# ESP32_USBC.net
KiCad netlist of a schematic drawn in Altium Designer
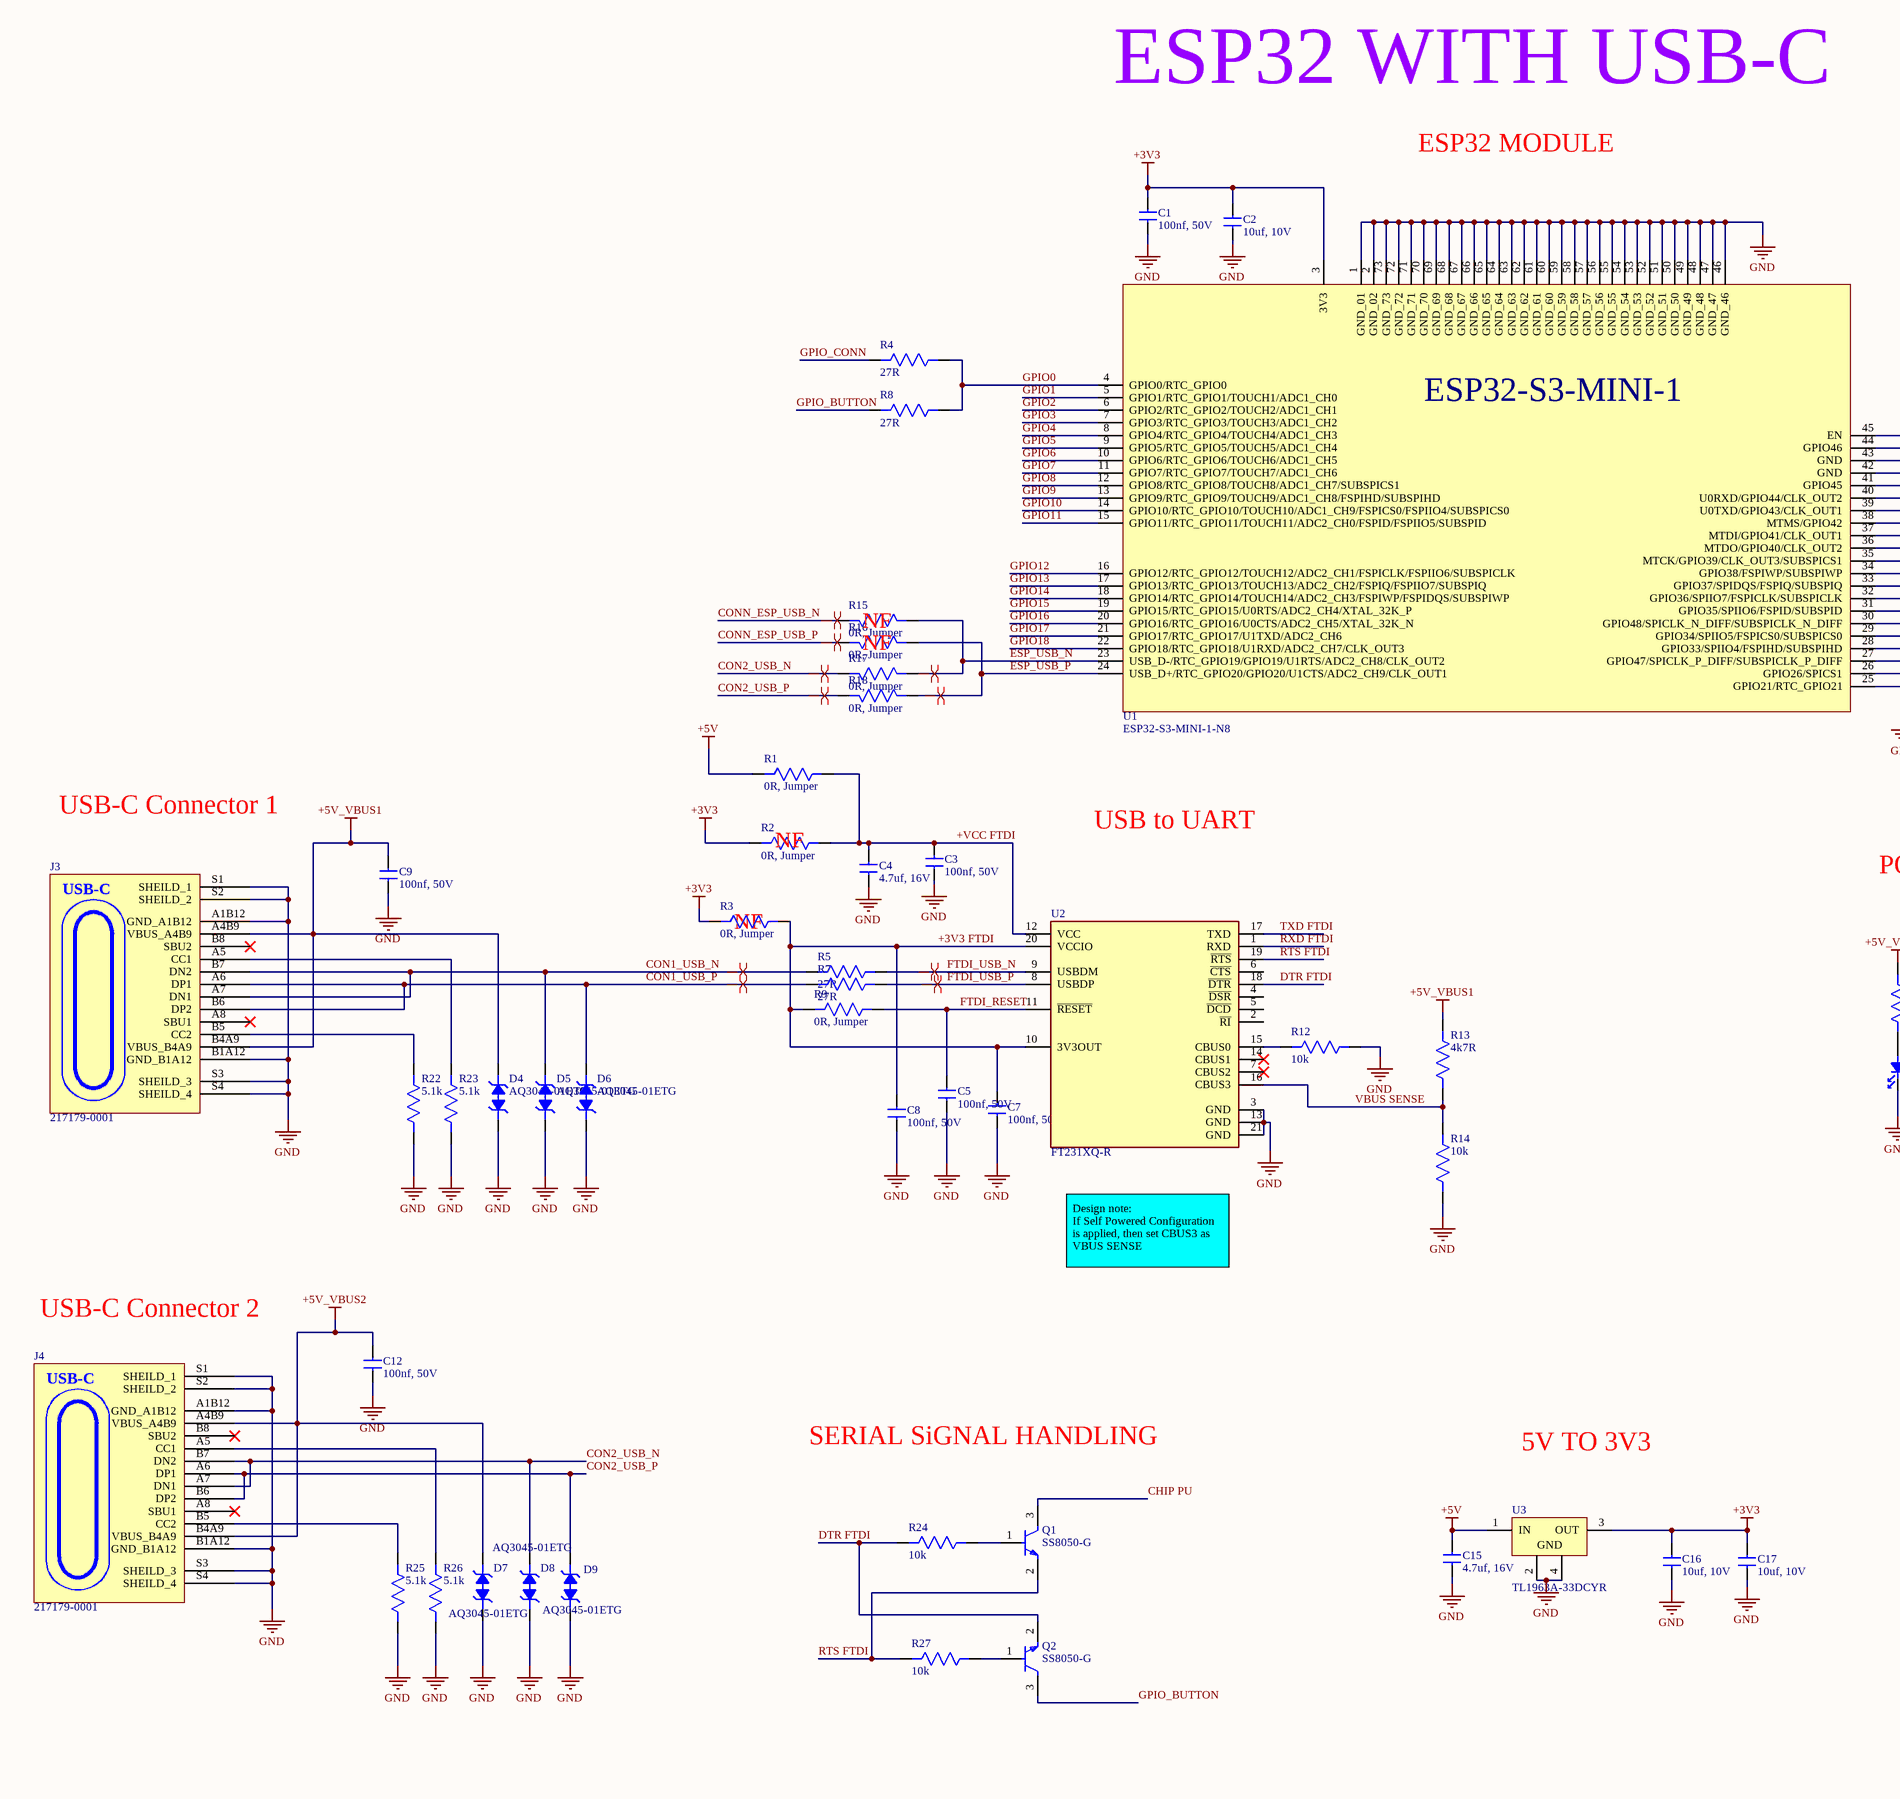
[diagram p0: ESP32_USBC.SchDoc, left]
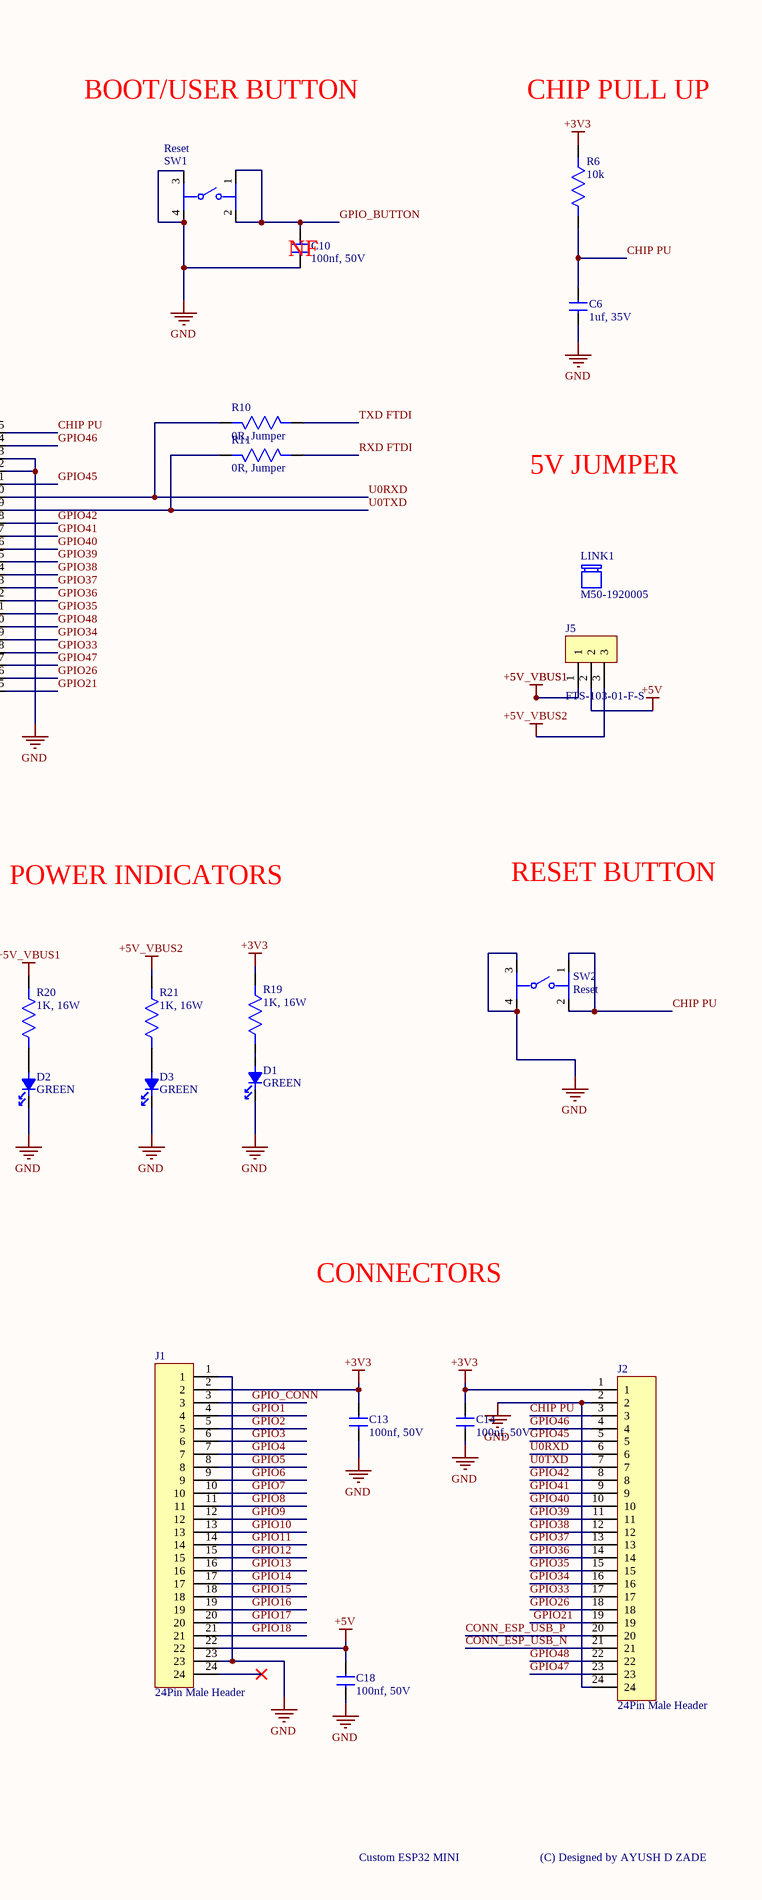
[diagram p1: ESP32_USBC.SchDoc, right]

(export (version "E")
  (design (tool "Eeschema 10.0.6"))
  (components
    (comp (ref "C1")
      (value "100nf, 50V")
      (footprint "CAPC1005X70N")
      (description "CAP CER 0.1UF 50V X7R 0402")
      (fields
        (field (name "MANUFACTURER") "Samsung Electro-Mechanics")
        (field (name "MANUFACTURER PART NUMBER") "CL05B104KB5NNWC")
      )
      (libsource (lib "Schlib") (part "CL05B104KB5NNWC"))
    )
    (comp (ref "C2")
      (value "10uf, 10V")
      (footprint "CAPC1005X70N")
      (description "CAP CER 10UF 10V X5R 0402")
      (fields
        (field (name "MANUFACTURER") "Samsung Electro-Mechanics")
        (field (name "MANUFACTURER PART NUMBER") "CL05A106MP5NRNC")
      )
      (libsource (lib "Schlib") (part "CL05A106MP5NRNC"))
    )
    (comp (ref "C3")
      (value "100nf, 50V")
      (footprint "CAPC1005X70N")
      (description "CAP CER 0.1UF 50V X7R 0402")
      (fields
        (field (name "MANUFACTURER") "Samsung Electro-Mechanics")
        (field (name "MANUFACTURER PART NUMBER") "CL05B104KB5NNWC")
      )
      (libsource (lib "Schlib") (part "CL05B104KB5NNWC"))
    )
    (comp (ref "C4")
      (value "4.7uf, 16V")
      (footprint "CAPC1005X70N")
      (description "4.7 µF ±20% 16V Ceramic Capacitor X5R 0402 (1005 Metric)")
      (fields
        (field (name "MANUFACTURER") "Samsung")
        (field (name "MANUFACTURER PART NUMBER") "CL05A475MO5NUNC")
      )
      (libsource (lib "Schlib") (part "CL05A475MO5NUNC"))
    )
    (comp (ref "C5")
      (value "100nf, 50V")
      (footprint "CAPC1005X70N")
      (description "CAP CER 0.1UF 50V X7R 0402")
      (fields
        (field (name "MANUFACTURER") "Samsung Electro-Mechanics")
        (field (name "MANUFACTURER PART NUMBER") "CL05B104KB5NNWC")
      )
      (libsource (lib "Schlib") (part "CL05B104KB5NNWC"))
    )
    (comp (ref "C6")
      (value "1uf, 35V")
      (footprint "CAPC1005X70N")
      (description "CAP CER 1UF 35V X5R 0402")
      (fields
        (field (name "MANUFACTURER") "Samsung Electro-Mechanics")
        (field (name "MANUFACTURER PART NUMBER") "CL05A105KL5NRNC")
      )
      (libsource (lib "Schlib") (part "CL05A105KL5NRNC"))
    )
    (comp (ref "C7")
      (value "100nf, 50V")
      (footprint "CAPC1005X70N")
      (description "CAP CER 0.1UF 50V X7R 0402")
      (fields
        (field (name "MANUFACTURER") "Samsung Electro-Mechanics")
        (field (name "MANUFACTURER PART NUMBER") "CL05B104KB5NNWC")
      )
      (libsource (lib "Schlib") (part "CL05B104KB5NNWC"))
    )
    (comp (ref "C8")
      (value "100nf, 50V")
      (footprint "CAPC1005X70N")
      (description "CAP CER 0.1UF 50V X7R 0402")
      (fields
        (field (name "MANUFACTURER") "Samsung Electro-Mechanics")
        (field (name "MANUFACTURER PART NUMBER") "CL05B104KB5NNWC")
      )
      (libsource (lib "Schlib") (part "CL05B104KB5NNWC"))
    )
    (comp (ref "C9")
      (value "100nf, 50V")
      (footprint "CAPC1005X70N")
      (description "CAP CER 0.1UF 50V X7R 0402")
      (fields
        (field (name "MANUFACTURER") "Samsung Electro-Mechanics")
        (field (name "MANUFACTURER PART NUMBER") "CL05B104KB5NNWC")
      )
      (libsource (lib "Schlib") (part "CL05B104KB5NNWC"))
    )
    (comp (ref "C10")
      (value "100nf, 50V")
      (footprint "CAPC1005X70N")
      (description "CAP CER 0.1UF 50V X7R 0402")
      (fields
        (field (name "MANUFACTURER") "Samsung Electro-Mechanics")
        (field (name "MANUFACTURER PART NUMBER") "CL05B104KB5NNWC")
      )
      (libsource (lib "Schlib") (part "CL05B104KB5NNWC"))
    )
    (comp (ref "C12")
      (value "100nf, 50V")
      (footprint "CAPC1005X70N")
      (description "CAP CER 0.1UF 50V X7R 0402")
      (fields
        (field (name "MANUFACTURER") "Samsung Electro-Mechanics")
        (field (name "MANUFACTURER PART NUMBER") "CL05B104KB5NNWC")
      )
      (libsource (lib "Schlib") (part "CL05B104KB5NNWC"))
    )
    (comp (ref "C13")
      (value "100nf, 50V")
      (footprint "CAPC1005X70N")
      (description "CAP CER 0.1UF 50V X7R 0402")
      (fields
        (field (name "MANUFACTURER") "Samsung Electro-Mechanics")
        (field (name "MANUFACTURER PART NUMBER") "CL05B104KB5NNWC")
      )
      (libsource (lib "Schlib") (part "CL05B104KB5NNWC"))
    )
    (comp (ref "C14")
      (value "100nf, 50V")
      (footprint "CAPC1005X70N")
      (description "CAP CER 0.1UF 50V X7R 0402")
      (fields
        (field (name "MANUFACTURER") "Samsung Electro-Mechanics")
        (field (name "MANUFACTURER PART NUMBER") "CL05B104KB5NNWC")
      )
      (libsource (lib "Schlib") (part "CL05B104KB5NNWC"))
    )
    (comp (ref "C15")
      (value "4.7uf, 16V")
      (footprint "CAPC1005X70N")
      (description "4.7 µF ±20% 16V Ceramic Capacitor X5R 0402 (1005 Metric)")
      (fields
        (field (name "MANUFACTURER") "Samsung")
        (field (name "MANUFACTURER PART NUMBER") "CL05A475MO5NUNC")
      )
      (libsource (lib "Schlib") (part "CL05A475MO5NUNC"))
    )
    (comp (ref "C16")
      (value "10uf, 10V")
      (footprint "CAPC1005X70N")
      (description "CAP CER 10UF 10V X5R 0402")
      (fields
        (field (name "MANUFACTURER") "Samsung Electro-Mechanics")
        (field (name "MANUFACTURER PART NUMBER") "CL05A106MP5NRNC")
      )
      (libsource (lib "Schlib") (part "CL05A106MP5NRNC"))
    )
    (comp (ref "C17")
      (value "10uf, 10V")
      (footprint "CAPC1005X70N")
      (description "CAP CER 10UF 10V X5R 0402")
      (fields
        (field (name "MANUFACTURER") "Samsung Electro-Mechanics")
        (field (name "MANUFACTURER PART NUMBER") "CL05A106MP5NRNC")
      )
      (libsource (lib "Schlib") (part "CL05A106MP5NRNC"))
    )
    (comp (ref "C18")
      (value "100nf, 50V")
      (footprint "CAPC1005X70N")
      (description "CAP CER 0.1UF 50V X7R 0402")
      (fields
        (field (name "MANUFACTURER") "Samsung Electro-Mechanics")
        (field (name "MANUFACTURER PART NUMBER") "CL05B104KB5NNWC")
      )
      (libsource (lib "Schlib") (part "CL05B104KB5NNWC"))
    )
    (comp (ref "D1")
      (value "GREEN")
      (footprint "LEDC1005X35N")
      (description "LED YLW-GRN 0402 SMD")
      (fields
        (field (name "MANUFACTURER") "Vishay")
        (field (name "MANUFACTURER PART NUMBER") "VLMG1500-GS08")
      )
      (libsource (lib "Schlib") (part "VLMG1500-GS08"))
    )
    (comp (ref "D2")
      (value "GREEN")
      (footprint "LEDC1005X35N")
      (description "LED YLW-GRN 0402 SMD")
      (fields
        (field (name "MANUFACTURER") "Vishay")
        (field (name "MANUFACTURER PART NUMBER") "VLMG1500-GS08")
      )
      (libsource (lib "Schlib") (part "VLMG1500-GS08"))
    )
    (comp (ref "D3")
      (value "GREEN")
      (footprint "LEDC1005X35N")
      (description "LED YLW-GRN 0402 SMD")
      (fields
        (field (name "MANUFACTURER") "Vishay")
        (field (name "MANUFACTURER PART NUMBER") "VLMG1500-GS08")
      )
      (libsource (lib "Schlib") (part "VLMG1500-GS08"))
    )
    (comp (ref "D4")
      (value "AQ3045-01ETG")
      (footprint "SOD882")
      (description "TVS DIODE 5.3VWM 12VC SOD882")
      (fields (field (name "MANUFACTURER") "Littelfuse") (field (name "LCSC PART NO.") "C3710326"))
      (libsource (lib "Schlib") (part "AQ3045-01ETG"))
    )
    (comp (ref "D5")
      (value "AQ3045-01ETG")
      (footprint "SOD882")
      (description "TVS DIODE 5.3VWM 12VC SOD882")
      (fields (field (name "MANUFACTURER") "Littelfuse") (field (name "LCSC PART NO.") "C3710326"))
      (libsource (lib "Schlib") (part "AQ3045-01ETG"))
    )
    (comp (ref "D6")
      (value "AQ3045-01ETG")
      (footprint "SOD882")
      (description "TVS DIODE 5.3VWM 12VC SOD882")
      (fields (field (name "MANUFACTURER") "Littelfuse") (field (name "LCSC PART NO.") "C3710326"))
      (libsource (lib "Schlib") (part "AQ3045-01ETG"))
    )
    (comp (ref "D7")
      (value "AQ3045-01ETG")
      (footprint "SOD882")
      (description "TVS DIODE 5.3VWM 12VC SOD882")
      (fields (field (name "MANUFACTURER") "Littelfuse") (field (name "LCSC PART NO.") "C3710326"))
      (libsource (lib "Schlib") (part "AQ3045-01ETG"))
    )
    (comp (ref "D8")
      (value "AQ3045-01ETG")
      (footprint "SOD882")
      (description "TVS DIODE 5.3VWM 12VC SOD882")
      (fields (field (name "MANUFACTURER") "Littelfuse") (field (name "LCSC PART NO.") "C3710326"))
      (libsource (lib "Schlib") (part "AQ3045-01ETG"))
    )
    (comp (ref "D9")
      (value "AQ3045-01ETG")
      (footprint "SOD882")
      (description "TVS DIODE 5.3VWM 12VC SOD882")
      (fields (field (name "MANUFACTURER") "Littelfuse") (field (name "LCSC PART NO.") "C3710326"))
      (libsource (lib "Schlib") (part "AQ3045-01ETG"))
    )
    (comp (ref "J1")
      (value "24Pin Male Header")
      (footprint "HDR_01x24_2.54mm")
      (description "CONN HEADER VERT 24POS 2.54MM")
      (fields (field (name "MANUFACTURER") "Molex") (field (name "MANUFACTURER PART NUMBER") "22-28-4245"))
      (libsource (lib "") (part "0022284245_1"))
    )
    (comp (ref "J2")
      (value "24Pin Male Header")
      (footprint "HDR_01x24_2.54mm")
      (description "CONN HEADER VERT 24POS 2.54MM")
      (fields (field (name "MANUFACTURER") "Molex") (field (name "MANUFACTURER PART NUMBER") "22-28-4245"))
      (libsource (lib "Schlib") (part "0022284245"))
    )
    (comp (ref "J3")
      (value "217179-0001")
      (footprint "FP-2171790001-MFG")
      (description "CONN RCP USB2.0 TYP C 24P SMD RA")
      (fields (field (name "MANUFACTURER") "Molex") (field (name "LCSC PART NO.") "C3197684"))
      (libsource (lib "Schlib") (part "217179-0001"))
    )
    (comp (ref "J4")
      (value "217179-0001")
      (footprint "FP-2171790001-MFG")
      (description "CONN RCP USB2.0 TYP C 24P SMD RA")
      (fields (field (name "MANUFACTURER") "Molex") (field (name "LCSC PART NO.") "C3197684"))
      (libsource (lib "Schlib") (part "217179-0001"))
    )
    (comp (ref "J5")
      (value "FTS-103-01-F-S")
      (footprint "HDR_01x03_1.27")
      (description "CONN HEADER VERT 3POS 1.27MM")
      (fields (field (name "MANUFACTURER") "Samtec") (field (name "LCSC PART NO.") "C3333578"))
      (libsource (lib "Schlib") (part "FTS-103-01-F-S"))
    )
    (comp (ref "LINK1")
      (value "M50-1920005")
      (description "CONN SHUNT 1.27MM RED")
      (fields (field (name "MANUFACTURER") "Harwin") (field (name "LCSC PART NO.") "C6985646"))
      (libsource (lib "Schlib") (part "M50-1920005"))
    )
    (comp (ref "Q1")
      (value "SS8050-G")
      (footprint "FP-SS8050-G-IPC_B")
      (description "TRANS NPN 25V 1.5A SOT-23-3")
      (fields (field (name "MANUFACTURER") "Comchip") (field (name "LCSC PART NO.") "C164886"))
      (libsource (lib "Schlib") (part "SS8050-G"))
    )
    (comp (ref "Q2")
      (value "SS8050-G")
      (footprint "FP-SS8050-G-IPC_B")
      (description "TRANS NPN 25V 1.5A SOT-23-3")
      (fields (field (name "MANUFACTURER") "Comchip") (field (name "LCSC PART NO.") "C164886"))
      (libsource (lib "Schlib") (part "SS8050-G"))
    )
    (comp (ref "R1")
      (value "0R, Jumper")
      (footprint "RESC1005X37N")
      (description "RES 0 OHM JUMPER 1/16W 0402")
      (fields
        (field (name "MANUFACTURER") "Yageo")
        (field (name "MANUFACTURER PART NUMBER") "RC0402FR-070RL")
      )
      (libsource (lib "Schlib") (part "RC0402FR-070RL"))
    )
    (comp (ref "R2")
      (value "0R, Jumper")
      (footprint "RESC1005X37N")
      (description "RES 0 OHM JUMPER 1/16W 0402")
      (fields
        (field (name "MANUFACTURER") "Yageo")
        (field (name "MANUFACTURER PART NUMBER") "RC0402FR-070RL")
      )
      (libsource (lib "Schlib") (part "RC0402FR-070RL"))
    )
    (comp (ref "R3")
      (value "0R, Jumper")
      (footprint "RESC1005X37N")
      (description "RES 0 OHM JUMPER 1/16W 0402")
      (fields
        (field (name "MANUFACTURER") "Yageo")
        (field (name "MANUFACTURER PART NUMBER") "RC0402FR-070RL")
      )
      (libsource (lib "Schlib") (part "RC0402FR-070RL"))
    )
    (comp (ref "R4")
      (value "27R")
      (footprint "RESC1005X37N")
      (description "RES 27 OHM 1% 1/16W 0402")
      (fields
        (field (name "MANUFACTURER") "Yageo")
        (field (name "MANUFACTURER PART NUMBER") "RC0402FR-0727RL")
      )
      (libsource (lib "Schlib") (part "RC0402FR-0727RL"))
    )
    (comp (ref "R5")
      (value "27R")
      (footprint "RESC1005X37N")
      (description "RES 27 OHM 1% 1/16W 0402")
      (fields
        (field (name "MANUFACTURER") "Yageo")
        (field (name "MANUFACTURER PART NUMBER") "RC0402FR-0727RL")
      )
      (libsource (lib "Schlib") (part "RC0402FR-0727RL"))
    )
    (comp (ref "R6")
      (value "10k")
      (footprint "RESC1005X37N")
      (description "RES SMD 10K OHM 1% 1/16W 0402")
      (fields
        (field (name "MANUFACTURER") "Yageo Group")
        (field (name "MANUFACTURER PART NUMBER") "AC0402FR-0710KL")
      )
      (libsource (lib "Schlib") (part "AC0402FR-0710KL"))
    )
    (comp (ref "R7")
      (value "27R")
      (footprint "RESC1005X37N")
      (description "RES 27 OHM 1% 1/16W 0402")
      (fields
        (field (name "MANUFACTURER") "Yageo")
        (field (name "MANUFACTURER PART NUMBER") "RC0402FR-0727RL")
      )
      (libsource (lib "Schlib") (part "RC0402FR-0727RL"))
    )
    (comp (ref "R8")
      (value "27R")
      (footprint "RESC1005X37N")
      (description "RES 27 OHM 1% 1/16W 0402")
      (fields
        (field (name "MANUFACTURER") "Yageo")
        (field (name "MANUFACTURER PART NUMBER") "RC0402FR-0727RL")
      )
      (libsource (lib "Schlib") (part "RC0402FR-0727RL"))
    )
    (comp (ref "R9")
      (value "0R, Jumper")
      (footprint "RESC1005X37N")
      (description "RES 0 OHM JUMPER 1/16W 0402")
      (fields
        (field (name "MANUFACTURER") "Yageo")
        (field (name "MANUFACTURER PART NUMBER") "RC0402FR-070RL")
      )
      (libsource (lib "Schlib") (part "RC0402FR-070RL"))
    )
    (comp (ref "R10")
      (value "0R, Jumper")
      (footprint "RESC1005X37N")
      (description "RES 0 OHM JUMPER 1/16W 0402")
      (fields
        (field (name "MANUFACTURER") "Yageo")
        (field (name "MANUFACTURER PART NUMBER") "RC0402FR-070RL")
      )
      (libsource (lib "Schlib") (part "RC0402FR-070RL"))
    )
    (comp (ref "R11")
      (value "0R, Jumper")
      (footprint "RESC1005X37N")
      (description "RES 0 OHM JUMPER 1/16W 0402")
      (fields
        (field (name "MANUFACTURER") "Yageo")
        (field (name "MANUFACTURER PART NUMBER") "RC0402FR-070RL")
      )
      (libsource (lib "Schlib") (part "RC0402FR-070RL"))
    )
    (comp (ref "R12")
      (value "10k")
      (footprint "RESC1005X37N")
      (description "RES SMD 10K OHM 1% 1/16W 0402")
      (fields
        (field (name "MANUFACTURER") "Yageo Group")
        (field (name "MANUFACTURER PART NUMBER") "AC0402FR-0710KL")
      )
      (libsource (lib "Schlib") (part "AC0402FR-0710KL"))
    )
    (comp (ref "R13")
      (value "4k7R")
      (footprint "RESC1005X37N")
      (description "RES 4.7K OHM 1% 1/16W 0402")
      (fields
        (field (name "MANUFACTURER") "Yageo")
        (field (name "MANUFACTURER PART NUMBER") "RC0402FR-074K7L")
      )
      (libsource (lib "Schlib") (part "RC0402FR-074K7L"))
    )
    (comp (ref "R14")
      (value "10k")
      (footprint "RESC1005X37N")
      (description "RES SMD 10K OHM 1% 1/16W 0402")
      (fields
        (field (name "MANUFACTURER") "Yageo Group")
        (field (name "MANUFACTURER PART NUMBER") "AC0402FR-0710KL")
      )
      (libsource (lib "Schlib") (part "AC0402FR-0710KL"))
    )
    (comp (ref "R15")
      (value "0R, Jumper")
      (footprint "RESC1005X37N")
      (description "RES 0 OHM JUMPER 1/16W 0402")
      (fields
        (field (name "MANUFACTURER") "Yageo")
        (field (name "MANUFACTURER PART NUMBER") "RC0402FR-070RL")
      )
      (libsource (lib "Schlib") (part "RC0402FR-070RL"))
    )
    (comp (ref "R16")
      (value "0R, Jumper")
      (footprint "RESC1005X37N")
      (description "RES 0 OHM JUMPER 1/16W 0402")
      (fields
        (field (name "MANUFACTURER") "Yageo")
        (field (name "MANUFACTURER PART NUMBER") "RC0402FR-070RL")
      )
      (libsource (lib "Schlib") (part "RC0402FR-070RL"))
    )
    (comp (ref "R17")
      (value "0R, Jumper")
      (footprint "RESC1005X37N")
      (description "RES 0 OHM JUMPER 1/16W 0402")
      (fields
        (field (name "MANUFACTURER") "Yageo")
        (field (name "MANUFACTURER PART NUMBER") "RC0402FR-070RL")
      )
      (libsource (lib "Schlib") (part "RC0402FR-070RL"))
    )
    (comp (ref "R18")
      (value "0R, Jumper")
      (footprint "RESC1005X37N")
      (description "RES 0 OHM JUMPER 1/16W 0402")
      (fields
        (field (name "MANUFACTURER") "Yageo")
        (field (name "MANUFACTURER PART NUMBER") "RC0402FR-070RL")
      )
      (libsource (lib "Schlib") (part "RC0402FR-070RL"))
    )
    (comp (ref "R19")
      (value "1K, 16W")
      (footprint "RESC1005X37N")
      (description "RES 1K OHM 1% 1/16W 0402")
      (fields
        (field (name "MANUFACTURER") "Yageo")
        (field (name "MANUFACTURER PART NUMBER") "RC0402FR-071KL")
      )
      (libsource (lib "Schlib") (part "RC0402FR-071KL"))
    )
    (comp (ref "R20")
      (value "1K, 16W")
      (footprint "RESC1005X37N")
      (description "RES 1K OHM 1% 1/16W 0402")
      (fields
        (field (name "MANUFACTURER") "Yageo")
        (field (name "MANUFACTURER PART NUMBER") "RC0402FR-071KL")
      )
      (libsource (lib "Schlib") (part "RC0402FR-071KL"))
    )
    (comp (ref "R21")
      (value "1K, 16W")
      (footprint "RESC1005X37N")
      (description "RES 1K OHM 1% 1/16W 0402")
      (fields
        (field (name "MANUFACTURER") "Yageo")
        (field (name "MANUFACTURER PART NUMBER") "RC0402FR-071KL")
      )
      (libsource (lib "Schlib") (part "RC0402FR-071KL"))
    )
    (comp (ref "R22")
      (value "5.1k")
      (footprint "RESC1005X37N")
      (description "RES SMD 5.1K OHM 1% 1/16W 0402")
      (fields
        (field (name "MANUFACTURER") "Yageo")
        (field (name "MANUFACTURER PART NUMBER") "AC0402FR-075K1L")
      )
      (libsource (lib "Schlib") (part "AC0402FR-075K1L"))
    )
    (comp (ref "R23")
      (value "5.1k")
      (footprint "RESC1005X37N")
      (description "RES SMD 5.1K OHM 1% 1/16W 0402")
      (fields
        (field (name "MANUFACTURER") "Yageo")
        (field (name "MANUFACTURER PART NUMBER") "AC0402FR-075K1L")
      )
      (libsource (lib "Schlib") (part "AC0402FR-075K1L"))
    )
    (comp (ref "R24")
      (value "10k")
      (footprint "RESC1005X37N")
      (description "RES SMD 10K OHM 1% 1/16W 0402")
      (fields
        (field (name "MANUFACTURER") "Yageo Group")
        (field (name "MANUFACTURER PART NUMBER") "AC0402FR-0710KL")
      )
      (libsource (lib "Schlib") (part "AC0402FR-0710KL"))
    )
    (comp (ref "R25")
      (value "5.1k")
      (footprint "RESC1005X37N")
      (description "RES SMD 5.1K OHM 1% 1/16W 0402")
      (fields
        (field (name "MANUFACTURER") "Yageo")
        (field (name "MANUFACTURER PART NUMBER") "AC0402FR-075K1L")
      )
      (libsource (lib "Schlib") (part "AC0402FR-075K1L"))
    )
    (comp (ref "R26")
      (value "5.1k")
      (footprint "RESC1005X37N")
      (description "RES SMD 5.1K OHM 1% 1/16W 0402")
      (fields
        (field (name "MANUFACTURER") "Yageo")
        (field (name "MANUFACTURER PART NUMBER") "AC0402FR-075K1L")
      )
      (libsource (lib "Schlib") (part "AC0402FR-075K1L"))
    )
    (comp (ref "R27")
      (value "10k")
      (footprint "RESC1005X37N")
      (description "RES SMD 10K OHM 1% 1/16W 0402")
      (fields
        (field (name "MANUFACTURER") "Yageo Group")
        (field (name "MANUFACTURER PART NUMBER") "AC0402FR-0710KL")
      )
      (libsource (lib "Schlib") (part "AC0402FR-0710KL"))
    )
    (comp (ref "SW1")
      (value "Reset")
      (footprint "FP-PTS645SH50SMTR92LFS-MFG")
      (description "SWITCH TACTILE SPST-NO 0.05A 12V")
      (fields
        (field (name "MANUFACTURER") "C&K Components")
        (field (name "MANUFACTURER PART NUMBER") "PTS645SH50SMTR92LFS")
      )
      (libsource (lib "Schlib") (part "PTS645SH50SMTR92LFS"))
    )
    (comp (ref "SW2")
      (value "Reset")
      (footprint "FP-PTS645SH50SMTR92LFS-MFG")
      (description "SWITCH TACTILE SPST-NO 0.05A 12V")
      (fields
        (field (name "MANUFACTURER") "C&K Components")
        (field (name "MANUFACTURER PART NUMBER") "PTS645SH50SMTR92LFS")
      )
      (libsource (lib "Schlib") (part "PTS645SH50SMTR92LFS"))
    )
    (comp (ref "U1")
      (value "ESP32-S3-MINI-1-N8")
      (footprint "XCVR_ESP32-S3-MINI-1-N8")
      (description "SMD module, ESP32-S3FN8, 8 MB SPI flash, PCB antenna")
      (fields (field (name "MANUFACTURER") "Espressif Systems") (field (name "LCSC PART NO.") "C2913206"))
      (libsource (lib "Schlib") (part "ESP32-S3-MINI-1-N8"))
    )
    (comp (ref "U2")
      (value "FT231XQ-R")
      (footprint "FP-QFN-20-IPC_B")
      (description "IC USB SERIAL FULL UART 20QFN")
      (fields (field (name "MANUFACTURER") "FTDI") (field (name "LCSC PART NO.") "C132159"))
      (libsource (lib "Schlib") (part "FT231XQ-R"))
    )
    (comp (ref "U3")
      (value "TL1963A-33DCYR")
      (footprint "DCY0004A_N")
      (description "IC REG LIN 3.3V 1.5A SOT-223-4")
      (fields (field (name "MANUFACTURER") "Texas Instruments") (field (name "LCSC PART NO.") "C181262"))
      (libsource (lib "Schlib") (part "TL1963A-33DCYR"))
    )
  )
  (nets
    (net (code "1") (name "+3V3") (class "Default")
      (node (ref "C1") (pin "2") (pinfunction "2_2") (pintype "passive"))
      (node (ref "C13") (pin "2") (pinfunction "2_2") (pintype "passive"))
      (node (ref "C14") (pin "2") (pinfunction "2_2") (pintype "passive"))
      (node (ref "C16") (pin "2") (pinfunction "2_2") (pintype "passive"))
      (node (ref "C17") (pin "2") (pinfunction "2_2") (pintype "passive"))
      (node (ref "C2") (pin "2") (pinfunction "2_2") (pintype "passive"))
      (node (ref "J1") (pin "2") (pinfunction "2_2") (pintype "passive"))
      (node (ref "J2") (pin "1") (pinfunction "1_1") (pintype "passive"))
      (node (ref "R19") (pin "2") (pinfunction "2_2") (pintype "passive"))
      (node (ref "R2") (pin "1") (pinfunction "1_1") (pintype "passive"))
      (node (ref "R3") (pin "1") (pinfunction "1_1") (pintype "passive"))
      (node (ref "R6") (pin "2") (pinfunction "2_2") (pintype "passive"))
      (node (ref "U1") (pin "3") (pinfunction "3V3_3") (pintype "passive"))
      (node (ref "U3") (pin "3") (pinfunction "OUT_3") (pintype "power_in"))
    )
    (net (code "2") (name "+5V") (class "Default")
      (node (ref "C15") (pin "2") (pinfunction "2_2") (pintype "passive"))
      (node (ref "C18") (pin "2") (pinfunction "2_2") (pintype "passive"))
      (node (ref "J1") (pin "22") (pinfunction "22_22") (pintype "passive"))
      (node (ref "J5") (pin "2") (pinfunction "2_2") (pintype "passive"))
      (node (ref "R1") (pin "1") (pinfunction "1_1") (pintype "passive"))
      (node (ref "U3") (pin "1") (pinfunction "IN_1") (pintype "power_in"))
    )
    (net (code "3") (name "+5V_VBUS1") (class "Default")
      (node (ref "C9") (pin "2") (pinfunction "2_2") (pintype "passive"))
      (node (ref "D4") (pin "2") (pinfunction "2_2") (pintype "passive"))
      (node (ref "J3") (pin "A4B9") (pinfunction "VBUS_A4B9_A4B9") (pintype "passive"))
      (node (ref "J3") (pin "B4A9") (pinfunction "VBUS_B4A9_B4A9") (pintype "passive"))
      (node (ref "J5") (pin "1") (pinfunction "1_1") (pintype "passive"))
      (node (ref "R13") (pin "2") (pinfunction "2_2") (pintype "passive"))
      (node (ref "R20") (pin "2") (pinfunction "2_2") (pintype "passive"))
    )
    (net (code "4") (name "+5V_VBUS2") (class "Default")
      (node (ref "C12") (pin "2") (pinfunction "2_2") (pintype "passive"))
      (node (ref "D7") (pin "2") (pinfunction "2_2") (pintype "passive"))
      (node (ref "J4") (pin "A4B9") (pinfunction "VBUS_A4B9_A4B9") (pintype "passive"))
      (node (ref "J4") (pin "B4A9") (pinfunction "VBUS_B4A9_B4A9") (pintype "passive"))
      (node (ref "J5") (pin "3") (pinfunction "3_3") (pintype "passive"))
      (node (ref "R21") (pin "2") (pinfunction "2_2") (pintype "passive"))
    )
    (net (code "5") (name "/+3V3 FTDI") (class "Default")
      (node (ref "C7") (pin "2") (pinfunction "2_2") (pintype "passive"))
      (node (ref "C8") (pin "2") (pinfunction "2_2") (pintype "passive"))
      (node (ref "R3") (pin "2") (pinfunction "2_2") (pintype "passive"))
      (node (ref "R9") (pin "1") (pinfunction "1_1") (pintype "passive"))
      (node (ref "U2") (pin "10") (pinfunction "3V3OUT_10") (pintype "passive"))
      (node (ref "U2") (pin "20") (pinfunction "VCCIO_20") (pintype "passive"))
    )
    (net (code "6") (name "/+VCC FTDI") (class "Default")
      (node (ref "C3") (pin "2") (pinfunction "2_2") (pintype "passive"))
      (node (ref "C4") (pin "2") (pinfunction "2_2") (pintype "passive"))
      (node (ref "R1") (pin "2") (pinfunction "2_2") (pintype "passive"))
      (node (ref "R2") (pin "2") (pinfunction "2_2") (pintype "passive"))
      (node (ref "U2") (pin "12") (pinfunction "VCC_12") (pintype "passive"))
    )
    (net (code "7") (name "/CHIP PU") (class "Default")
      (node (ref "C6") (pin "2") (pinfunction "2_2") (pintype "passive"))
      (node (ref "J2") (pin "3") (pinfunction "3_3") (pintype "passive"))
      (node (ref "Q1") (pin "3") (pinfunction "C_3") (pintype "passive"))
      (node (ref "R6") (pin "1") (pinfunction "1_1") (pintype "passive"))
      (node (ref "SW2") (pin "1") (pinfunction "1_1") (pintype "passive"))
      (node (ref "SW2") (pin "2") (pinfunction "2_2") (pintype "passive"))
      (node (ref "U1") (pin "45") (pinfunction "EN_45") (pintype "passive"))
    )
    (net (code "8") (name "/CON1_USB_N") (class "Default")
      (node (ref "D5") (pin "2") (pinfunction "2_2") (pintype "passive"))
      (node (ref "J3") (pin "A7") (pinfunction "DN1_A7") (pintype "passive"))
      (node (ref "J3") (pin "B7") (pinfunction "DN2_B7") (pintype "passive"))
      (node (ref "R5") (pin "1") (pinfunction "1_1") (pintype "passive"))
    )
    (net (code "9") (name "/CON1_USB_P") (class "Default")
      (node (ref "D6") (pin "2") (pinfunction "2_2") (pintype "passive"))
      (node (ref "J3") (pin "A6") (pinfunction "DP1_A6") (pintype "passive"))
      (node (ref "J3") (pin "B6") (pinfunction "DP2_B6") (pintype "passive"))
      (node (ref "R7") (pin "1") (pinfunction "1_1") (pintype "passive"))
    )
    (net (code "10") (name "/CON2_USB_N") (class "Default")
      (node (ref "D8") (pin "2") (pinfunction "2_2") (pintype "passive"))
      (node (ref "J4") (pin "A7") (pinfunction "DN1_A7") (pintype "passive"))
      (node (ref "J4") (pin "B7") (pinfunction "DN2_B7") (pintype "passive"))
      (node (ref "R17") (pin "2") (pinfunction "2_2") (pintype "passive"))
    )
    (net (code "11") (name "/CON2_USB_P") (class "Default")
      (node (ref "D9") (pin "2") (pinfunction "2_2") (pintype "passive"))
      (node (ref "J4") (pin "A6") (pinfunction "DP1_A6") (pintype "passive"))
      (node (ref "J4") (pin "B6") (pinfunction "DP2_B6") (pintype "passive"))
      (node (ref "R18") (pin "2") (pinfunction "2_2") (pintype "passive"))
    )
    (net (code "12") (name "/CONN_ESP_USB_N") (class "Default")
      (node (ref "J2") (pin "21") (pinfunction "21_21") (pintype "passive"))
      (node (ref "R15") (pin "2") (pinfunction "2_2") (pintype "passive"))
    )
    (net (code "13") (name "/CONN_ESP_USB_P") (class "Default")
      (node (ref "J2") (pin "20") (pinfunction "20_20") (pintype "passive"))
      (node (ref "R16") (pin "2") (pinfunction "2_2") (pintype "passive"))
    )
    (net (code "14") (name "/DTR FTDI") (class "Default")
      (node (ref "Q2") (pin "2") (pinfunction "E_2") (pintype "passive"))
      (node (ref "R24") (pin "1") (pinfunction "1_1") (pintype "passive"))
      (node (ref "U2") (pin "18") (pinfunction "~{DTR}_18") (pintype "passive"))
    )
    (net (code "15") (name "/ESP_USB_N") (class "Default")
      (node (ref "R15") (pin "1") (pinfunction "1_1") (pintype "passive"))
      (node (ref "R17") (pin "1") (pinfunction "1_1") (pintype "passive"))
      (node (ref "U1") (pin "23") (pinfunction "USB_D-/RTC_GPIO19/GPIO19/U1RTS/ADC2_CH8/CLK_OUT2_23") (pintype "passive"))
    )
    (net (code "16") (name "/ESP_USB_P") (class "Default")
      (node (ref "R16") (pin "1") (pinfunction "1_1") (pintype "passive"))
      (node (ref "R18") (pin "1") (pinfunction "1_1") (pintype "passive"))
      (node (ref "U1") (pin "24") (pinfunction "USB_D+/RTC_GPIO20/GPIO20/U1CTS/ADC2_CH9/CLK_OUT1_24") (pintype "passive"))
    )
    (net (code "17") (name "/FTDI_RESET") (class "Default")
      (node (ref "C5") (pin "2") (pinfunction "2_2") (pintype "passive"))
      (node (ref "R9") (pin "2") (pinfunction "2_2") (pintype "passive"))
      (node (ref "U2") (pin "11") (pinfunction "~{RESET}_11") (pintype "passive"))
    )
    (net (code "18") (name "/FTDI_USB_N") (class "Default")
      (node (ref "R5") (pin "2") (pinfunction "2_2") (pintype "passive"))
      (node (ref "U2") (pin "9") (pinfunction "USBDM_9") (pintype "passive"))
    )
    (net (code "19") (name "/FTDI_USB_P") (class "Default")
      (node (ref "R7") (pin "2") (pinfunction "2_2") (pintype "passive"))
      (node (ref "U2") (pin "8") (pinfunction "USBDP_8") (pintype "passive"))
    )
    (net (code "20") (name "/GPIO0") (class "Default")
      (node (ref "R4") (pin "2") (pinfunction "2_2") (pintype "passive"))
      (node (ref "R8") (pin "2") (pinfunction "2_2") (pintype "passive"))
      (node (ref "U1") (pin "4") (pinfunction "GPIO0/RTC_GPIO0_4") (pintype "passive"))
    )
    (net (code "21") (name "/GPIO1") (class "Default")
      (node (ref "J1") (pin "4") (pinfunction "4_4") (pintype "passive"))
      (node (ref "U1") (pin "5") (pinfunction "GPIO1/RTC_GPIO1/TOUCH1/ADC1_CH0_5") (pintype "passive"))
    )
    (net (code "22") (name "/GPIO2") (class "Default")
      (node (ref "J1") (pin "5") (pinfunction "5_5") (pintype "passive"))
      (node (ref "U1") (pin "6") (pinfunction "GPIO2/RTC_GPIO2/TOUCH2/ADC1_CH1_6") (pintype "passive"))
    )
    (net (code "23") (name "/GPIO3") (class "Default")
      (node (ref "J1") (pin "6") (pinfunction "6_6") (pintype "passive"))
      (node (ref "U1") (pin "7") (pinfunction "GPIO3/RTC_GPIO3/TOUCH3/ADC1_CH2_7") (pintype "passive"))
    )
    (net (code "24") (name "/GPIO4") (class "Default")
      (node (ref "J1") (pin "7") (pinfunction "7_7") (pintype "passive"))
      (node (ref "U1") (pin "8") (pinfunction "GPIO4/RTC_GPIO4/TOUCH4/ADC1_CH3_8") (pintype "passive"))
    )
    (net (code "25") (name "/GPIO5") (class "Default")
      (node (ref "J1") (pin "8") (pinfunction "8_8") (pintype "passive"))
      (node (ref "U1") (pin "9") (pinfunction "GPIO5/RTC_GPIO5/TOUCH5/ADC1_CH4_9") (pintype "passive"))
    )
    (net (code "26") (name "/GPIO6") (class "Default")
      (node (ref "J1") (pin "9") (pinfunction "9_9") (pintype "passive"))
      (node (ref "U1") (pin "10") (pinfunction "GPIO6/RTC_GPIO6/TOUCH6/ADC1_CH5_10") (pintype "passive"))
    )
    (net (code "27") (name "/GPIO7") (class "Default")
      (node (ref "J1") (pin "10") (pinfunction "10_10") (pintype "passive"))
      (node (ref "U1") (pin "11") (pinfunction "GPIO7/RTC_GPIO7/TOUCH7/ADC1_CH6_11") (pintype "passive"))
    )
    (net (code "28") (name "/GPIO8") (class "Default")
      (node (ref "J1") (pin "11") (pinfunction "11_11") (pintype "passive"))
      (node (ref "U1") (pin "12") (pinfunction "GPIO8/RTC_GPIO8/TOUCH8/ADC1_CH7/SUBSPICS1_12") (pintype "passive"))
    )
    (net (code "29") (name "/GPIO9") (class "Default")
      (node (ref "J1") (pin "12") (pinfunction "12_12") (pintype "passive"))
      (node (ref "U1") (pin "13") (pinfunction "GPIO9/RTC_GPIO9/TOUCH9/ADC1_CH8/FSPIHD/SUBSPIHD_13") (pintype "passive"))
    )
    (net (code "30") (name "/GPIO10") (class "Default")
      (node (ref "J1") (pin "13") (pinfunction "13_13") (pintype "passive"))
      (node (ref "U1") (pin "14") (pinfunction "GPIO10/RTC_GPIO10/TOUCH10/ADC1_CH9/FSPICS0/FSPIIO4/SUBSPICS0_14") (pintype "passive"))
    )
    (net (code "31") (name "/GPIO11") (class "Default")
      (node (ref "J1") (pin "14") (pinfunction "14_14") (pintype "passive"))
      (node (ref "U1") (pin "15") (pinfunction "GPIO11/RTC_GPIO11/TOUCH11/ADC2_CH0/FSPID/FSPIIO5/SUBSPID_15") (pintype "passive"))
    )
    (net (code "32") (name "/GPIO12") (class "Default")
      (node (ref "J1") (pin "15") (pinfunction "15_15") (pintype "passive"))
      (node (ref "U1") (pin "16") (pinfunction "GPIO12/RTC_GPIO12/TOUCH12/ADC2_CH1/FSPICLK/FSPIIO6/SUBSPICLK_16") (pintype "passive"))
    )
    (net (code "33") (name "/GPIO13") (class "Default")
      (node (ref "J1") (pin "16") (pinfunction "16_16") (pintype "passive"))
      (node (ref "U1") (pin "17") (pinfunction "GPIO13/RTC_GPIO13/TOUCH13/ADC2_CH2/FSPIQ/FSPIIO7/SUBSPIQ_17") (pintype "passive"))
    )
    (net (code "34") (name "/GPIO14") (class "Default")
      (node (ref "J1") (pin "17") (pinfunction "17_17") (pintype "passive"))
      (node (ref "U1") (pin "18") (pinfunction "GPIO14/RTC_GPIO14/TOUCH14/ADC2_CH3/FSPIWP/FSPIDQS/SUBSPIWP_18") (pintype "passive"))
    )
    (net (code "35") (name "/GPIO15") (class "Default")
      (node (ref "J1") (pin "18") (pinfunction "18_18") (pintype "passive"))
      (node (ref "U1") (pin "19") (pinfunction "GPIO15/RTC_GPIO15/U0RTS/ADC2_CH4/XTAL_32K_P_19") (pintype "passive"))
    )
    (net (code "36") (name "/GPIO16") (class "Default")
      (node (ref "J1") (pin "19") (pinfunction "19_19") (pintype "passive"))
      (node (ref "U1") (pin "20") (pinfunction "GPIO16/RTC_GPIO16/U0CTS/ADC2_CH5/XTAL_32K_N_20") (pintype "passive"))
    )
    (net (code "37") (name "/GPIO17") (class "Default")
      (node (ref "J1") (pin "20") (pinfunction "20_20") (pintype "passive"))
      (node (ref "U1") (pin "21") (pinfunction "GPIO17/RTC_GPIO17/U1TXD/ADC2_CH6_21") (pintype "passive"))
    )
    (net (code "38") (name "/GPIO18") (class "Default")
      (node (ref "J1") (pin "21") (pinfunction "21_21") (pintype "passive"))
      (node (ref "U1") (pin "22") (pinfunction "GPIO18/RTC_GPIO18/U1RXD/ADC2_CH7/CLK_OUT3_22") (pintype "passive"))
    )
    (net (code "39") (name "/GPIO21") (class "Default")
      (node (ref "J2") (pin "19") (pinfunction "19_19") (pintype "passive"))
      (node (ref "U1") (pin "25") (pinfunction "GPIO21/RTC_GPIO21_25") (pintype "passive"))
    )
    (net (code "40") (name "/GPIO26") (class "Default")
      (node (ref "J2") (pin "18") (pinfunction "18_18") (pintype "passive"))
      (node (ref "U1") (pin "26") (pinfunction "GPIO26/SPICS1_26") (pintype "passive"))
    )
    (net (code "41") (name "/GPIO33") (class "Default")
      (node (ref "J2") (pin "17") (pinfunction "17_17") (pintype "passive"))
      (node (ref "U1") (pin "28") (pinfunction "GPIO33/SPIIO4/FSPIHD/SUBSPIHD_28") (pintype "passive"))
    )
    (net (code "42") (name "/GPIO34") (class "Default")
      (node (ref "J2") (pin "16") (pinfunction "16_16") (pintype "passive"))
      (node (ref "U1") (pin "29") (pinfunction "GPIO34/SPIIO5/FSPICS0/SUBSPICS0_29") (pintype "passive"))
    )
    (net (code "43") (name "/GPIO35") (class "Default")
      (node (ref "J2") (pin "15") (pinfunction "15_15") (pintype "passive"))
      (node (ref "U1") (pin "31") (pinfunction "GPIO35/SPIIO6/FSPID/SUBSPID_31") (pintype "passive"))
    )
    (net (code "44") (name "/GPIO36") (class "Default")
      (node (ref "J2") (pin "14") (pinfunction "14_14") (pintype "passive"))
      (node (ref "U1") (pin "32") (pinfunction "GPIO36/SPIIO7/FSPICLK/SUBSPICLK_32") (pintype "passive"))
    )
    (net (code "45") (name "/GPIO37") (class "Default")
      (node (ref "J2") (pin "13") (pinfunction "13_13") (pintype "passive"))
      (node (ref "U1") (pin "33") (pinfunction "GPIO37/SPIDQS/FSPIQ/SUBSPIQ_33") (pintype "passive"))
    )
    (net (code "46") (name "/GPIO38") (class "Default")
      (node (ref "J2") (pin "12") (pinfunction "12_12") (pintype "passive"))
      (node (ref "U1") (pin "34") (pinfunction "GPIO38/FSPIWP/SUBSPIWP_34") (pintype "passive"))
    )
    (net (code "47") (name "/GPIO39") (class "Default")
      (node (ref "J2") (pin "11") (pinfunction "11_11") (pintype "passive"))
      (node (ref "U1") (pin "35") (pinfunction "MTCK/GPIO39/CLK_OUT3/SUBSPICS1_35") (pintype "passive"))
    )
    (net (code "48") (name "/GPIO40") (class "Default")
      (node (ref "J2") (pin "10") (pinfunction "10_10") (pintype "passive"))
      (node (ref "U1") (pin "36") (pinfunction "MTDO/GPIO40/CLK_OUT2_36") (pintype "passive"))
    )
    (net (code "49") (name "/GPIO41") (class "Default")
      (node (ref "J2") (pin "9") (pinfunction "9_9") (pintype "passive"))
      (node (ref "U1") (pin "37") (pinfunction "MTDI/GPIO41/CLK_OUT1_37") (pintype "passive"))
    )
    (net (code "50") (name "/GPIO42") (class "Default")
      (node (ref "J2") (pin "8") (pinfunction "8_8") (pintype "passive"))
      (node (ref "U1") (pin "38") (pinfunction "MTMS/GPIO42_38") (pintype "passive"))
    )
    (net (code "51") (name "/GPIO45") (class "Default")
      (node (ref "J2") (pin "5") (pinfunction "5_5") (pintype "passive"))
      (node (ref "U1") (pin "41") (pinfunction "GPIO45_41") (pintype "passive"))
    )
    (net (code "52") (name "/GPIO46") (class "Default")
      (node (ref "J2") (pin "4") (pinfunction "4_4") (pintype "passive"))
      (node (ref "U1") (pin "44") (pinfunction "GPIO46_44") (pintype "passive"))
    )
    (net (code "53") (name "/GPIO47") (class "Default")
      (node (ref "J2") (pin "23") (pinfunction "23_23") (pintype "passive"))
      (node (ref "U1") (pin "27") (pinfunction "GPIO47/SPICLK_P_DIFF/SUBSPICLK_P_DIFF_27") (pintype "passive"))
    )
    (net (code "54") (name "/GPIO48") (class "Default")
      (node (ref "J2") (pin "22") (pinfunction "22_22") (pintype "passive"))
      (node (ref "U1") (pin "30") (pinfunction "GPIO48/SPICLK_N_DIFF/SUBSPICLK_N_DIFF_30") (pintype "passive"))
    )
    (net (code "55") (name "/GPIO_BUTTON") (class "Default")
      (node (ref "C10") (pin "1") (pinfunction "1_1") (pintype "passive"))
      (node (ref "Q2") (pin "3") (pinfunction "C_3") (pintype "passive"))
      (node (ref "R8") (pin "1") (pinfunction "1_1") (pintype "passive"))
      (node (ref "SW1") (pin "1") (pinfunction "1_1") (pintype "passive"))
      (node (ref "SW1") (pin "2") (pinfunction "2_2") (pintype "passive"))
    )
    (net (code "56") (name "/GPIO_CONN") (class "Default")
      (node (ref "J1") (pin "3") (pinfunction "3_3") (pintype "passive"))
      (node (ref "R4") (pin "1") (pinfunction "1_1") (pintype "passive"))
    )
    (net (code "57") (name "/RTS FTDI") (class "Default")
      (node (ref "Q1") (pin "2") (pinfunction "E_2") (pintype "passive"))
      (node (ref "R27") (pin "1") (pinfunction "1_1") (pintype "passive"))
      (node (ref "U2") (pin "19") (pinfunction "~{RTS}_19") (pintype "passive"))
    )
    (net (code "58") (name "/RXD FTDI") (class "Default")
      (node (ref "R11") (pin "1") (pinfunction "1_1") (pintype "passive"))
      (node (ref "U2") (pin "1") (pinfunction "RXD_1") (pintype "passive"))
    )
    (net (code "59") (name "/TXD FTDI") (class "Default")
      (node (ref "R10") (pin "1") (pinfunction "1_1") (pintype "passive"))
      (node (ref "U2") (pin "17") (pinfunction "TXD_17") (pintype "passive"))
    )
    (net (code "60") (name "/U0RXD") (class "Default")
      (node (ref "J2") (pin "6") (pinfunction "6_6") (pintype "passive"))
      (node (ref "R10") (pin "2") (pinfunction "2_2") (pintype "passive"))
      (node (ref "U1") (pin "40") (pinfunction "U0RXD/GPIO44/CLK_OUT2_40") (pintype "passive"))
    )
    (net (code "61") (name "/U0TXD") (class "Default")
      (node (ref "J2") (pin "7") (pinfunction "7_7") (pintype "passive"))
      (node (ref "R11") (pin "2") (pinfunction "2_2") (pintype "passive"))
      (node (ref "U1") (pin "39") (pinfunction "U0TXD/GPIO43/CLK_OUT1_39") (pintype "passive"))
    )
    (net (code "62") (name "/VBUS SENSE") (class "Default")
      (node (ref "R13") (pin "1") (pinfunction "1_1") (pintype "passive"))
      (node (ref "R14") (pin "2") (pinfunction "2_2") (pintype "passive"))
      (node (ref "U2") (pin "16") (pinfunction "CBUS3_16") (pintype "passive"))
    )
    (net (code "63") (name "GND") (class "Default")
      (node (ref "C1") (pin "1") (pinfunction "1_1") (pintype "passive"))
      (node (ref "C10") (pin "2") (pinfunction "2_2") (pintype "passive"))
      (node (ref "C12") (pin "1") (pinfunction "1_1") (pintype "passive"))
      (node (ref "C13") (pin "1") (pinfunction "1_1") (pintype "passive"))
      (node (ref "C14") (pin "1") (pinfunction "1_1") (pintype "passive"))
      (node (ref "C15") (pin "1") (pinfunction "1_1") (pintype "passive"))
      (node (ref "C16") (pin "1") (pinfunction "1_1") (pintype "passive"))
      (node (ref "C17") (pin "1") (pinfunction "1_1") (pintype "passive"))
      (node (ref "C18") (pin "1") (pinfunction "1_1") (pintype "passive"))
      (node (ref "C2") (pin "1") (pinfunction "1_1") (pintype "passive"))
      (node (ref "C3") (pin "1") (pinfunction "1_1") (pintype "passive"))
      (node (ref "C4") (pin "1") (pinfunction "1_1") (pintype "passive"))
      (node (ref "C5") (pin "1") (pinfunction "1_1") (pintype "passive"))
      (node (ref "C6") (pin "1") (pinfunction "1_1") (pintype "passive"))
      (node (ref "C7") (pin "1") (pinfunction "1_1") (pintype "passive"))
      (node (ref "C8") (pin "1") (pinfunction "1_1") (pintype "passive"))
      (node (ref "C9") (pin "1") (pinfunction "1_1") (pintype "passive"))
      (node (ref "D1") (pin "1") (pinfunction "1_1") (pintype "passive"))
      (node (ref "D2") (pin "1") (pinfunction "1_1") (pintype "passive"))
      (node (ref "D3") (pin "1") (pinfunction "1_1") (pintype "passive"))
      (node (ref "D4") (pin "1") (pinfunction "1_1") (pintype "passive"))
      (node (ref "D5") (pin "1") (pinfunction "1_1") (pintype "passive"))
      (node (ref "D6") (pin "1") (pinfunction "1_1") (pintype "passive"))
      (node (ref "D7") (pin "1") (pinfunction "1_1") (pintype "passive"))
      (node (ref "D8") (pin "1") (pinfunction "1_1") (pintype "passive"))
      (node (ref "D9") (pin "1") (pinfunction "1_1") (pintype "passive"))
      (node (ref "J1") (pin "1") (pinfunction "1_1") (pintype "passive"))
      (node (ref "J1") (pin "23") (pinfunction "23_23") (pintype "passive"))
      (node (ref "J2") (pin "2") (pinfunction "2_2") (pintype "passive"))
      (node (ref "J2") (pin "24") (pinfunction "24_24") (pintype "passive"))
      (node (ref "J3") (pin "A1B12") (pinfunction "GND_A1B12_A1B12") (pintype "passive"))
      (node (ref "J3") (pin "B1A12") (pinfunction "GND_B1A12_B1A12") (pintype "passive"))
      (node (ref "J3") (pin "S1") (pinfunction "SHEILD_1_S1") (pintype "passive"))
      (node (ref "J3") (pin "S2") (pinfunction "SHEILD_2_S2") (pintype "passive"))
      (node (ref "J3") (pin "S3") (pinfunction "SHEILD_3_S3") (pintype "passive"))
      (node (ref "J3") (pin "S4") (pinfunction "SHEILD_4_S4") (pintype "passive"))
      (node (ref "J4") (pin "A1B12") (pinfunction "GND_A1B12_A1B12") (pintype "passive"))
      (node (ref "J4") (pin "B1A12") (pinfunction "GND_B1A12_B1A12") (pintype "passive"))
      (node (ref "J4") (pin "S1") (pinfunction "SHEILD_1_S1") (pintype "passive"))
      (node (ref "J4") (pin "S2") (pinfunction "SHEILD_2_S2") (pintype "passive"))
      (node (ref "J4") (pin "S3") (pinfunction "SHEILD_3_S3") (pintype "passive"))
      (node (ref "J4") (pin "S4") (pinfunction "SHEILD_4_S4") (pintype "passive"))
      (node (ref "R12") (pin "2") (pinfunction "2_2") (pintype "passive"))
      (node (ref "R14") (pin "1") (pinfunction "1_1") (pintype "passive"))
      (node (ref "R22") (pin "2") (pinfunction "2_2") (pintype "passive"))
      (node (ref "R23") (pin "2") (pinfunction "2_2") (pintype "passive"))
      (node (ref "R25") (pin "2") (pinfunction "2_2") (pintype "passive"))
      (node (ref "R26") (pin "2") (pinfunction "2_2") (pintype "passive"))
      (node (ref "SW1") (pin "3") (pinfunction "3_3") (pintype "passive"))
      (node (ref "SW1") (pin "4") (pinfunction "4_4") (pintype "passive"))
      (node (ref "SW2") (pin "3") (pinfunction "3_3") (pintype "passive"))
      (node (ref "SW2") (pin "4") (pinfunction "4_4") (pintype "passive"))
      (node (ref "U1") (pin "1") (pinfunction "GND_01_1") (pintype "passive"))
      (node (ref "U1") (pin "2") (pinfunction "GND_02_2") (pintype "passive"))
      (node (ref "U1") (pin "42") (pinfunction "GND_42") (pintype "passive"))
      (node (ref "U1") (pin "43") (pinfunction "GND_43") (pintype "passive"))
      (node (ref "U1") (pin "46") (pinfunction "GND_46_46") (pintype "passive"))
      (node (ref "U1") (pin "47") (pinfunction "GND_47_47") (pintype "passive"))
      (node (ref "U1") (pin "48") (pinfunction "GND_48_48") (pintype "passive"))
      (node (ref "U1") (pin "49") (pinfunction "GND_49_49") (pintype "passive"))
      (node (ref "U1") (pin "50") (pinfunction "GND_50_50") (pintype "passive"))
      (node (ref "U1") (pin "51") (pinfunction "GND_51_51") (pintype "passive"))
      (node (ref "U1") (pin "52") (pinfunction "GND_52_52") (pintype "passive"))
      (node (ref "U1") (pin "53") (pinfunction "GND_53_53") (pintype "passive"))
      (node (ref "U1") (pin "54") (pinfunction "GND_54_54") (pintype "passive"))
      (node (ref "U1") (pin "55") (pinfunction "GND_55_55") (pintype "passive"))
      (node (ref "U1") (pin "56") (pinfunction "GND_56_56") (pintype "passive"))
      (node (ref "U1") (pin "57") (pinfunction "GND_57_57") (pintype "passive"))
      (node (ref "U1") (pin "58") (pinfunction "GND_58_58") (pintype "passive"))
      (node (ref "U1") (pin "59") (pinfunction "GND_59_59") (pintype "passive"))
      (node (ref "U1") (pin "60") (pinfunction "GND_60_60") (pintype "passive"))
      (node (ref "U1") (pin "61") (pinfunction "GND_61_61") (pintype "passive"))
      (node (ref "U1") (pin "62") (pinfunction "GND_62_62") (pintype "passive"))
      (node (ref "U1") (pin "63") (pinfunction "GND_63_63") (pintype "passive"))
      (node (ref "U1") (pin "64") (pinfunction "GND_64_64") (pintype "passive"))
      (node (ref "U1") (pin "65") (pinfunction "GND_65_65") (pintype "passive"))
      (node (ref "U1") (pin "66") (pinfunction "GND_66_66") (pintype "passive"))
      (node (ref "U1") (pin "67") (pinfunction "GND_67_67") (pintype "passive"))
      (node (ref "U1") (pin "68") (pinfunction "GND_68_68") (pintype "passive"))
      (node (ref "U1") (pin "69") (pinfunction "GND_69_69") (pintype "passive"))
      (node (ref "U1") (pin "70") (pinfunction "GND_70_70") (pintype "passive"))
      (node (ref "U1") (pin "71") (pinfunction "GND_71_71") (pintype "passive"))
      (node (ref "U1") (pin "72") (pinfunction "GND_72_72") (pintype "passive"))
      (node (ref "U1") (pin "73") (pinfunction "GND_73_73") (pintype "passive"))
      (node (ref "U2") (pin "13") (pinfunction "GND_13") (pintype "passive"))
      (node (ref "U2") (pin "21") (pinfunction "GND_21") (pintype "passive"))
      (node (ref "U2") (pin "3") (pinfunction "GND_3") (pintype "passive"))
      (node (ref "U3") (pin "2") (pinfunction "GND_2") (pintype "power_in"))
      (node (ref "U3") (pin "4") (pinfunction "GND_4") (pintype "power_in"))
    )
    (net (code "64") (name "Net-(D1-Pad2)") (class "Default")
      (node (ref "D1") (pin "2") (pinfunction "2_2") (pintype "passive"))
      (node (ref "R19") (pin "1") (pinfunction "1_1") (pintype "passive"))
    )
    (net (code "65") (name "Net-(D2-Pad2)") (class "Default")
      (node (ref "D2") (pin "2") (pinfunction "2_2") (pintype "passive"))
      (node (ref "R20") (pin "1") (pinfunction "1_1") (pintype "passive"))
    )
    (net (code "66") (name "Net-(D3-Pad2)") (class "Default")
      (node (ref "D3") (pin "2") (pinfunction "2_2") (pintype "passive"))
      (node (ref "R21") (pin "1") (pinfunction "1_1") (pintype "passive"))
    )
    (net (code "67") (name "Net-(J3-CC1)") (class "Default")
      (node (ref "J3") (pin "A5") (pinfunction "CC1_A5") (pintype "passive"))
      (node (ref "R23") (pin "1") (pinfunction "1_1") (pintype "passive"))
    )
    (net (code "68") (name "Net-(J3-CC2)") (class "Default")
      (node (ref "J3") (pin "B5") (pinfunction "CC2_B5") (pintype "passive"))
      (node (ref "R22") (pin "1") (pinfunction "1_1") (pintype "passive"))
    )
    (net (code "69") (name "Net-(J4-CC1)") (class "Default")
      (node (ref "J4") (pin "A5") (pinfunction "CC1_A5") (pintype "passive"))
      (node (ref "R26") (pin "1") (pinfunction "1_1") (pintype "passive"))
    )
    (net (code "70") (name "Net-(J4-CC2)") (class "Default")
      (node (ref "J4") (pin "B5") (pinfunction "CC2_B5") (pintype "passive"))
      (node (ref "R25") (pin "1") (pinfunction "1_1") (pintype "passive"))
    )
    (net (code "71") (name "Net-(Q1-B)") (class "Default")
      (node (ref "Q1") (pin "1") (pinfunction "B_1") (pintype "passive"))
      (node (ref "R24") (pin "2") (pinfunction "2_2") (pintype "passive"))
    )
    (net (code "72") (name "Net-(Q2-B)") (class "Default")
      (node (ref "Q2") (pin "1") (pinfunction "B_1") (pintype "passive"))
      (node (ref "R27") (pin "2") (pinfunction "2_2") (pintype "passive"))
    )
    (net (code "73") (name "Net-(U2-CBUS0)") (class "Default")
      (node (ref "R12") (pin "1") (pinfunction "1_1") (pintype "passive"))
      (node (ref "U2") (pin "15") (pinfunction "CBUS0_15") (pintype "passive"))
    )
    (net (code "74") (name "unconnected-(J1-Pad24)") (class "Default")
      (node (ref "J1") (pin "24") (pinfunction "24_24") (pintype "passive+no_connect"))
    )
    (net (code "75") (name "unconnected-(J3-SBU1-PadA8)") (class "Default")
      (node (ref "J3") (pin "A8") (pinfunction "SBU1_A8") (pintype "passive+no_connect"))
    )
    (net (code "76") (name "unconnected-(J3-SBU2-PadB8)") (class "Default")
      (node (ref "J3") (pin "B8") (pinfunction "SBU2_B8") (pintype "passive+no_connect"))
    )
    (net (code "77") (name "unconnected-(J4-SBU1-PadA8)") (class "Default")
      (node (ref "J4") (pin "A8") (pinfunction "SBU1_A8") (pintype "passive+no_connect"))
    )
    (net (code "78") (name "unconnected-(J4-SBU2-PadB8)") (class "Default")
      (node (ref "J4") (pin "B8") (pinfunction "SBU2_B8") (pintype "passive+no_connect"))
    )
    (net (code "79") (name "unconnected-(U2-CBUS1-Pad14)") (class "Default")
      (node (ref "U2") (pin "14") (pinfunction "CBUS1_14") (pintype "passive+no_connect"))
    )
    (net (code "80") (name "unconnected-(U2-CBUS2-Pad7)") (class "Default")
      (node (ref "U2") (pin "7") (pinfunction "CBUS2_7") (pintype "passive+no_connect"))
    )
    (net (code "81") (name "unconnected-(U2-~{CTS}-Pad6)") (class "Default")
      (node (ref "U2") (pin "6") (pinfunction "~{CTS}_6") (pintype "passive"))
    )
    (net (code "82") (name "unconnected-(U2-~{DCD}-Pad5)") (class "Default")
      (node (ref "U2") (pin "5") (pinfunction "~{DCD}_5") (pintype "passive"))
    )
    (net (code "83") (name "unconnected-(U2-~{DSR}-Pad4)") (class "Default")
      (node (ref "U2") (pin "4") (pinfunction "~{DSR}_4") (pintype "passive"))
    )
    (net (code "84") (name "unconnected-(U2-~{RI}-Pad2)") (class "Default")
      (node (ref "U2") (pin "2") (pinfunction "~{RI}_2") (pintype "passive"))
    )
  )
)
